# SparkFun_Qwiic_Mini_UV_Sensor_AS7331.net
KiCad netlist of a schematic drawn in EAGLE
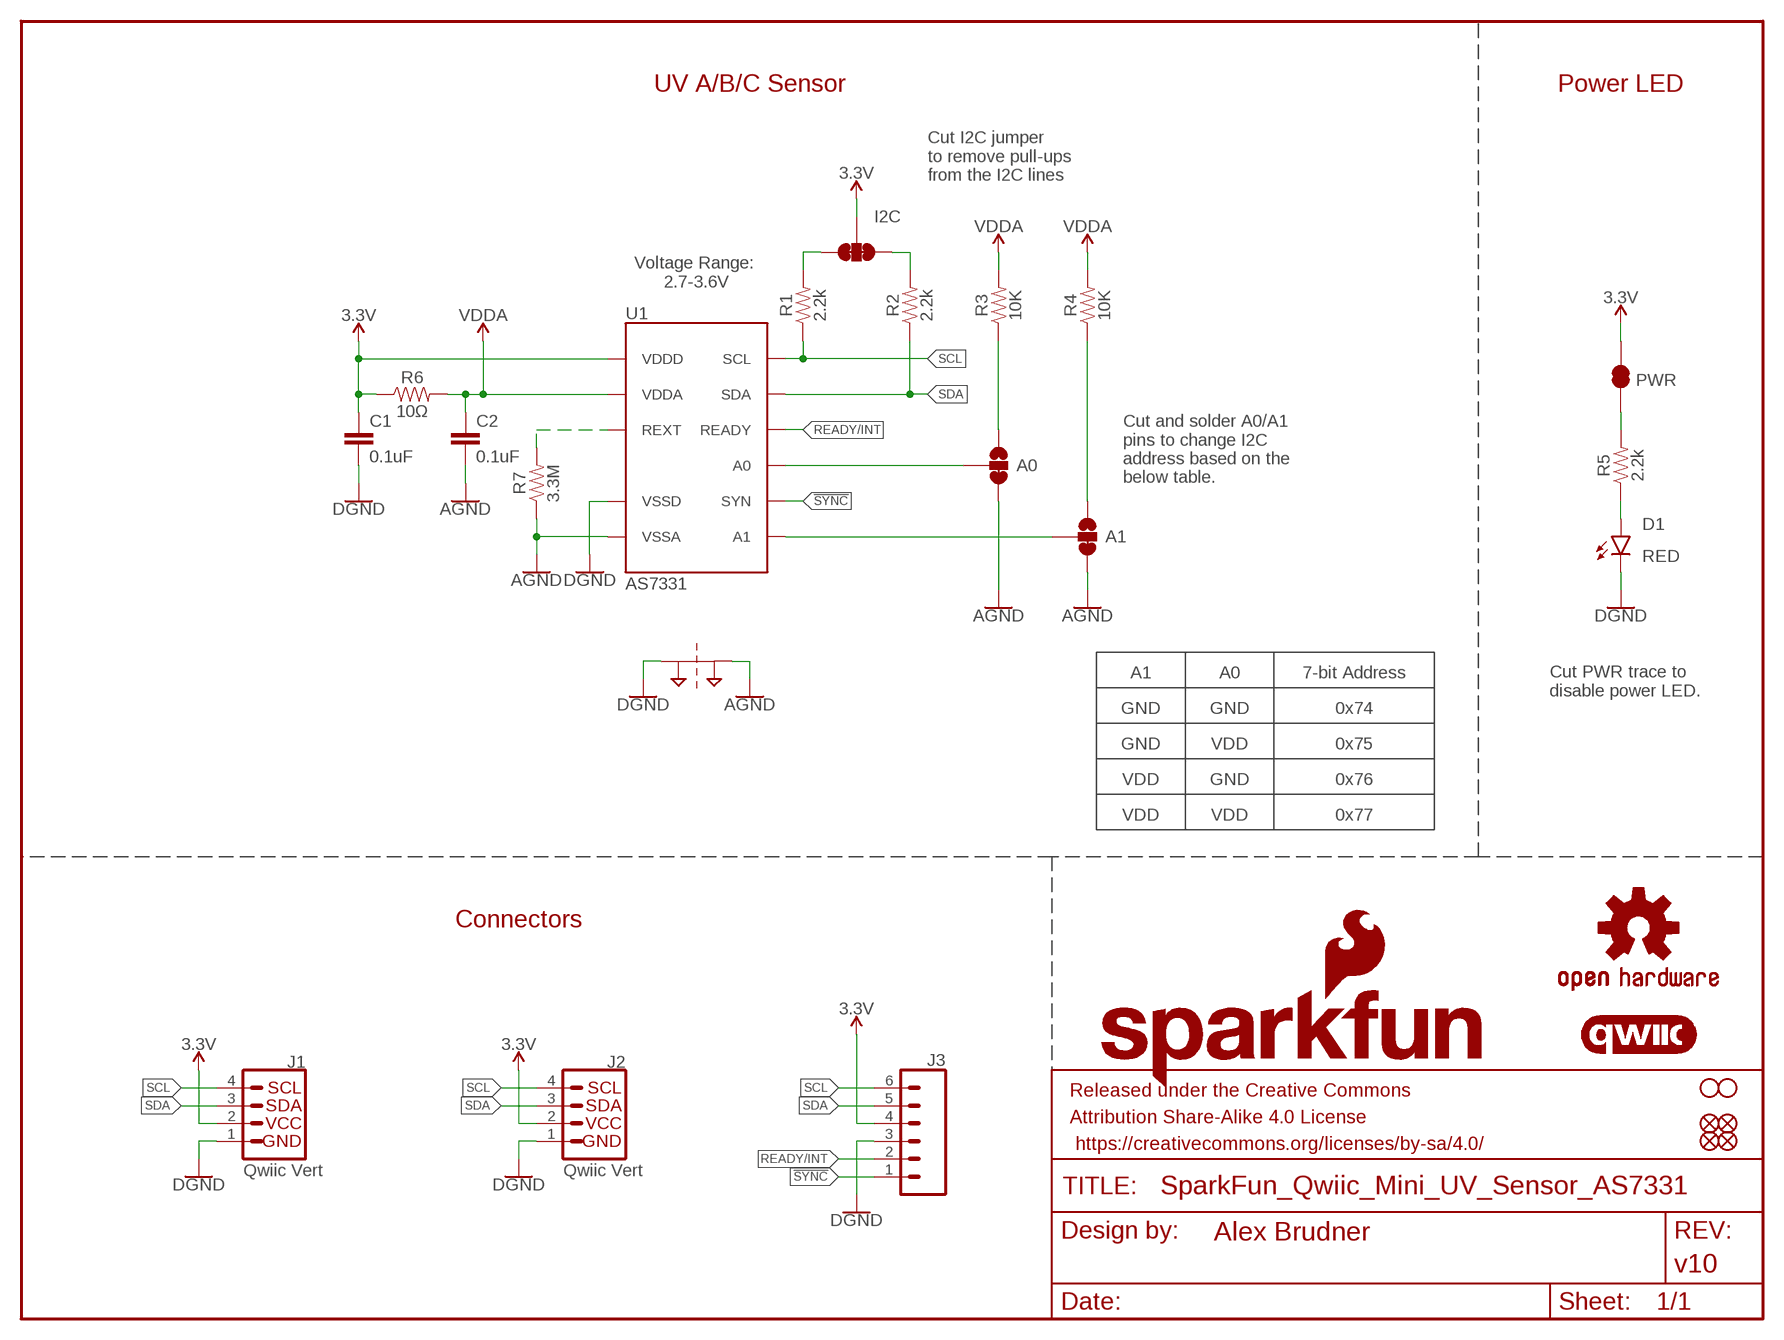
[diagram p0: schematic, sheet 1]

(export (version "E")
  (design (tool "Eeschema 10.0.6"))
  (components
    (comp (ref "A0")
      (value "JUMPER-SMT_3_1-NC_TRACE_SILK")
      (footprint "eagle-import:SMT-JUMPER_3_1-NC_TRACE_SILK")
      (libsource (lib "eagle-import") (part "JUMPER-SMT_3_1-NC_TRACE_SILK"))
    )
    (comp (ref "A1")
      (value "JUMPER-SMT_3_1-NC_TRACE_SILK")
      (footprint "eagle-import:SMT-JUMPER_3_1-NC_TRACE_SILK")
      (libsource (lib "eagle-import") (part "JUMPER-SMT_3_1-NC_TRACE_SILK"))
    )
    (comp (ref "C1")
      (value "0.1uF")
      (footprint "eagle-import:0402-TIGHT")
      (libsource (lib "eagle-import") (part "0.1UF-0402T-6.3V-10%-X7R"))
    )
    (comp (ref "C2")
      (value "0.1uF")
      (footprint "eagle-import:0402-TIGHT")
      (libsource (lib "eagle-import") (part "0.1UF-0402T-6.3V-10%-X7R"))
    )
    (comp (ref "D1")
      (value "RED")
      (footprint "eagle-import:LED-0402")
      (libsource (lib "eagle-import") (part "LED-RED_0402"))
    )
    (comp (ref "FD1")
      (value "FIDUCIALUFIDUCIAL")
      (footprint "eagle-import:FIDUCIAL-MICRO")
      (libsource (lib "eagle-import") (part "FIDUCIALUFIDUCIAL"))
    )
    (comp (ref "FD2")
      (value "FIDUCIALUFIDUCIAL")
      (footprint "eagle-import:FIDUCIAL-MICRO")
      (libsource (lib "eagle-import") (part "FIDUCIALUFIDUCIAL"))
    )
    (comp (ref "FD3")
      (value "FIDUCIALUFIDUCIAL")
      (footprint "eagle-import:FIDUCIAL-MICRO")
      (libsource (lib "eagle-import") (part "FIDUCIALUFIDUCIAL"))
    )
    (comp (ref "FD4")
      (value "FIDUCIALUFIDUCIAL")
      (footprint "eagle-import:FIDUCIAL-MICRO")
      (libsource (lib "eagle-import") (part "FIDUCIALUFIDUCIAL"))
    )
    (comp (ref "FRAME1")
      (value "FRAME-LETTER")
      (footprint "eagle-import:CREATIVE_COMMONS")
      (fields (field (name "DESIGNER") "Alex Brudner") (field (name "REV") "v10"))
      (libsource (lib "eagle-import") (part "FRAME-LETTER"))
    )
    (comp (ref "H1")
      (value "STAND-OFFTIGHT")
      (footprint "eagle-import:STAND-OFF-TIGHT")
      (libsource (lib "eagle-import") (part "STAND-OFFTIGHT"))
    )
    (comp (ref "H2")
      (value "STAND-OFFTIGHT")
      (footprint "eagle-import:STAND-OFF-TIGHT")
      (libsource (lib "eagle-import") (part "STAND-OFFTIGHT"))
    )
    (comp (ref "I2C")
      (value "JUMPER-SMT_3_2-NC_TRACE_SILK")
      (footprint "eagle-import:SMT-JUMPER_3_2-NC_TRACE_SILK")
      (libsource (lib "eagle-import") (part "JUMPER-SMT_3_2-NC_TRACE_SILK"))
    )
    (comp (ref "J1")
      (value "Qwiic Vert")
      (footprint "eagle-import:JST04_1MM_VERT")
      (libsource (lib "eagle-import") (part "QWIIC_CONNECTOR"))
    )
    (comp (ref "J2")
      (value "Qwiic Vert")
      (footprint "eagle-import:JST04_1MM_VERT")
      (libsource (lib "eagle-import") (part "QWIIC_CONNECTOR"))
    )
    (comp (ref "J3")
      (value "CONN_06NO_SILK_NO_POP")
      (footprint "eagle-import:1X06_NO_SILK")
      (libsource (lib "eagle-import") (part "CONN_06NO_SILK_NO_POP"))
    )
    (comp (ref "LOGO1")
      (value "SFE_LOGO_NAME.1_INCH")
      (footprint "eagle-import:SFE_LOGO_NAME_.1")
      (libsource (lib "eagle-import") (part "SFE_LOGO_NAME.1_INCH"))
    )
    (comp (ref "LOGO2")
      (value "QWIIC_LOGO_CONNECTOR")
      (footprint "eagle-import:QWIIC_5.5MM")
      (libsource (lib "eagle-import") (part "QWIIC_LOGO_CONNECTOR"))
    )
    (comp (ref "LOGO3")
      (value "OSHW-LOGOMINI")
      (footprint "eagle-import:OSHW-LOGO-MINI")
      (libsource (lib "eagle-import") (part "OSHW-LOGOMINI"))
    )
    (comp (ref "LOGO4")
      (value "SFE_LOGO_FLAME.1_INCH")
      (footprint "eagle-import:SFE_LOGO_FLAME_.1")
      (libsource (lib "eagle-import") (part "SFE_LOGO_FLAME.1_INCH"))
    )
    (comp (ref "PWR")
      (value "JUMPER-SMT_2_NC_TRACE_SILK")
      (footprint "eagle-import:SMT-JUMPER_2_NC_TRACE_SILK")
      (libsource (lib "eagle-import") (part "JUMPER-SMT_2_NC_TRACE_SILK"))
    )
    (comp (ref "R1")
      (value "2.2k")
      (footprint "eagle-import:0402-TIGHT")
      (libsource (lib "eagle-import") (part "2.2KOHM-0402T-1/16W-1%"))
    )
    (comp (ref "R2")
      (value "2.2k")
      (footprint "eagle-import:0402-TIGHT")
      (libsource (lib "eagle-import") (part "2.2KOHM-0402T-1/16W-1%"))
    )
    (comp (ref "R3")
      (value "10K")
      (footprint "eagle-import:0402-TIGHT")
      (libsource (lib "eagle-import") (part "10KOHM-0402-1/10W-0.1%"))
    )
    (comp (ref "R4")
      (value "10K")
      (footprint "eagle-import:0402-TIGHT")
      (libsource (lib "eagle-import") (part "10KOHM-0402-1/10W-0.1%"))
    )
    (comp (ref "R5")
      (value "2.2k")
      (footprint "eagle-import:0402-TIGHT")
      (libsource (lib "eagle-import") (part "2.2KOHM-0402T-1/16W-1%"))
    )
    (comp (ref "R6")
      (value "10Ω")
      (footprint "eagle-import:0402-TIGHT")
      (libsource (lib "eagle-import") (part "10OHM-0402-1/16W-5%"))
    )
    (comp (ref "R7")
      (value "3.3M")
      (footprint "eagle-import:1206")
      (libsource (lib "eagle-import") (part "3.3MOHM"))
    )
    (comp (ref "SUPPLYTIE1")
      (value "2PT_GND_TIE")
      (footprint "eagle-import:2PT_GND_TIE")
      (libsource (lib "eagle-import") (part "2PT_GND_TIE"))
    )
    (comp (ref "U1")
      (value "AS7331")
      (footprint "eagle-import:OLGA16")
      (libsource (lib "eagle-import") (part "UV_SENSOR_AS7331"))
    )
  )
  (nets
    (net (code "1") (name "/~{SYNC}") (class "Default")
      (node (ref "J3") (pin "1") (pinfunction "1_1") (pintype "passive"))
      (node (ref "U1") (pin "8") (pinfunction "SYN_8") (pintype "input"))
    )
    (net (code "2") (name "3.3V") (class "Default")
      (node (ref "C1") (pin "1") (pinfunction "1_1") (pintype "passive"))
      (node (ref "I2C") (pin "2") (pinfunction "2_2") (pintype "passive"))
      (node (ref "J1") (pin "2") (pinfunction "2_2") (pintype "power_in"))
      (node (ref "J2") (pin "2") (pinfunction "2_2") (pintype "power_in"))
      (node (ref "J3") (pin "4") (pinfunction "4_4") (pintype "passive"))
      (node (ref "PWR") (pin "2") (pinfunction "2_2") (pintype "passive"))
      (node (ref "R6") (pin "1") (pinfunction "1_1") (pintype "passive"))
      (node (ref "U1") (pin "10") (pinfunction "VDDD_10") (pintype "power_in"))
    )
    (net (code "3") (name "AGND") (class "Default")
      (node (ref "A0") (pin "3") (pinfunction "3_3") (pintype "passive"))
      (node (ref "A1") (pin "3") (pinfunction "3_3") (pintype "passive"))
      (node (ref "C2") (pin "2") (pinfunction "2_2") (pintype "passive"))
      (node (ref "R7") (pin "1") (pinfunction "1_1") (pintype "passive"))
      (node (ref "SUPPLYTIE1") (pin "P$2") (pinfunction "P$2_P$2") (pintype "bidirectional"))
      (node (ref "U1") (pin "1") (pinfunction "VSSA_1") (pintype "power_in"))
      (node (ref "U1") (pin "15") (pinfunction "VSSA_15") (pintype "power_in"))
      (node (ref "U1") (pin "16") (pinfunction "VSSA_16") (pintype "power_in"))
      (node (ref "U1") (pin "2") (pinfunction "VSSA_2") (pintype "power_in"))
      (node (ref "U1") (pin "5") (pinfunction "VSSA_5") (pintype "power_in"))
      (node (ref "U1") (pin "6") (pinfunction "VSSA_6") (pintype "power_in"))
    )
    (net (code "4") (name "DGND") (class "Default")
      (node (ref "C1") (pin "2") (pinfunction "2_2") (pintype "passive"))
      (node (ref "D1") (pin "C") (pinfunction "C_C") (pintype "passive"))
      (node (ref "J1") (pin "1") (pinfunction "1_1") (pintype "power_in"))
      (node (ref "J2") (pin "1") (pinfunction "1_1") (pintype "power_in"))
      (node (ref "J3") (pin "3") (pinfunction "3_3") (pintype "passive"))
      (node (ref "SUPPLYTIE1") (pin "P$1") (pinfunction "P$1_P$1") (pintype "bidirectional"))
      (node (ref "U1") (pin "11") (pinfunction "VSSD_11") (pintype "power_in"))
    )
    (net (code "5") (name "Net-(A0-Pad1)") (class "Default")
      (node (ref "A0") (pin "1") (pinfunction "1_1") (pintype "passive"))
      (node (ref "R3") (pin "1") (pinfunction "1_1") (pintype "passive"))
    )
    (net (code "6") (name "Net-(A1-Pad1)") (class "Default")
      (node (ref "A1") (pin "1") (pinfunction "1_1") (pintype "passive"))
      (node (ref "R4") (pin "1") (pinfunction "1_1") (pintype "passive"))
    )
    (net (code "7") (name "Net-(D1-PadA)") (class "Default")
      (node (ref "D1") (pin "A") (pinfunction "A_A") (pintype "passive"))
      (node (ref "R5") (pin "1") (pinfunction "1_1") (pintype "passive"))
    )
    (net (code "8") (name "Net-(I2C-Pad1)") (class "Default")
      (node (ref "I2C") (pin "1") (pinfunction "1_1") (pintype "passive"))
      (node (ref "R2") (pin "2") (pinfunction "2_2") (pintype "passive"))
    )
    (net (code "9") (name "Net-(I2C-Pad3)") (class "Default")
      (node (ref "I2C") (pin "3") (pinfunction "3_3") (pintype "passive"))
      (node (ref "R1") (pin "2") (pinfunction "2_2") (pintype "passive"))
    )
    (net (code "10") (name "Net-(PWR-Pad1)") (class "Default")
      (node (ref "PWR") (pin "1") (pinfunction "1_1") (pintype "passive"))
      (node (ref "R5") (pin "2") (pinfunction "2_2") (pintype "passive"))
    )
    (net (code "11") (name "Net-(U1-A0)") (class "Default")
      (node (ref "A0") (pin "2") (pinfunction "2_2") (pintype "passive"))
      (node (ref "U1") (pin "14") (pinfunction "A0_14") (pintype "input"))
    )
    (net (code "12") (name "Net-(U1-A1)") (class "Default")
      (node (ref "A1") (pin "2") (pinfunction "2_2") (pintype "passive"))
      (node (ref "U1") (pin "7") (pinfunction "A1_7") (pintype "input"))
    )
    (net (code "13") (name "Net-(U1-REXT)") (class "Default")
      (node (ref "R7") (pin "2") (pinfunction "2_2") (pintype "passive"))
      (node (ref "U1") (pin "4") (pinfunction "REXT_4") (pintype "bidirectional"))
    )
    (net (code "14") (name "READY{slash}INT") (class "Default")
      (node (ref "J3") (pin "2") (pinfunction "2_2") (pintype "passive"))
      (node (ref "U1") (pin "9") (pinfunction "READY_9") (pintype "output"))
    )
    (net (code "15") (name "SCL") (class "Default")
      (node (ref "J1") (pin "4") (pinfunction "4_4") (pintype "passive"))
      (node (ref "J2") (pin "4") (pinfunction "4_4") (pintype "passive"))
      (node (ref "J3") (pin "6") (pinfunction "6_6") (pintype "passive"))
      (node (ref "R1") (pin "1") (pinfunction "1_1") (pintype "passive"))
      (node (ref "U1") (pin "13") (pinfunction "SCL_13") (pintype "input"))
    )
    (net (code "16") (name "SDA") (class "Default")
      (node (ref "J1") (pin "3") (pinfunction "3_3") (pintype "passive"))
      (node (ref "J2") (pin "3") (pinfunction "3_3") (pintype "passive"))
      (node (ref "J3") (pin "5") (pinfunction "5_5") (pintype "passive"))
      (node (ref "R2") (pin "1") (pinfunction "1_1") (pintype "passive"))
      (node (ref "U1") (pin "12") (pinfunction "SDA_12") (pintype "bidirectional"))
    )
    (net (code "17") (name "VDDA") (class "Default")
      (node (ref "C2") (pin "1") (pinfunction "1_1") (pintype "passive"))
      (node (ref "R3") (pin "2") (pinfunction "2_2") (pintype "passive"))
      (node (ref "R4") (pin "2") (pinfunction "2_2") (pintype "passive"))
      (node (ref "R6") (pin "2") (pinfunction "2_2") (pintype "passive"))
      (node (ref "U1") (pin "3") (pinfunction "VDDA_3") (pintype "power_in"))
    )
  )
)
